# RS232-485.net
KiCad netlist of a schematic drawn in Altium Designer
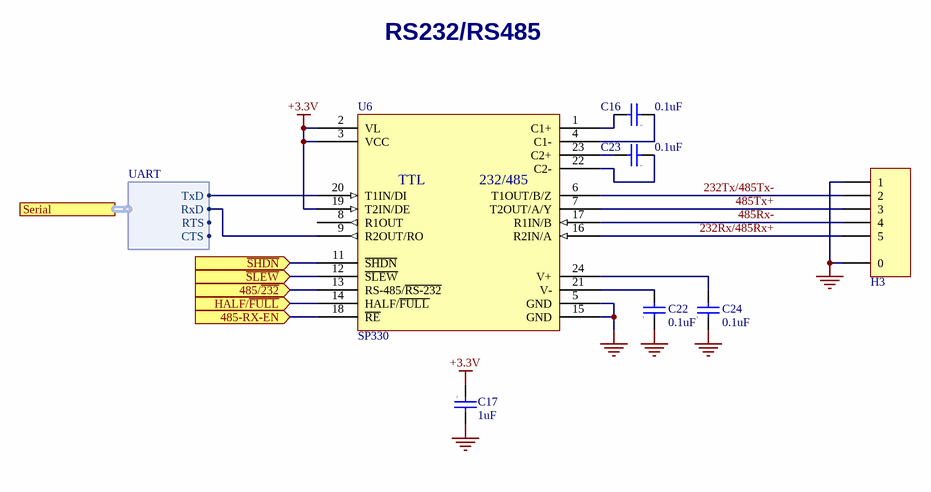
[diagram p0: RS232-485.SchDoc]

(export (version "E")
  (design (tool "Eeschema 10.0.6"))
  (components
    (comp (ref "C16")
      (value "0.1uF")
      (footprint "0402")
      (description "CAP CER .10UF 50V X7R 10% 0402")
      (fields
        (field (name "MANUFACTURER") "TDK Corporation")
        (field (name "MANUFACTURER PART NUMBER") "C1005X7R1H104K")
        (field (name "PUBLISHER") "Altium Limited")
      )
      (libsource (lib "General") (part "Cap"))
    )
    (comp (ref "C17")
      (value "1uF")
      (footprint "0603")
      (description "CAP CER 1UF 25V X7R 0603")
      (fields
        (field (name "MANUFACTURER") "Samsung")
        (field (name "MANUFACTURER PART NUMBER") "CL10B105KA8NNNC")
        (field (name "PUBLISHER") "Altium Limited")
      )
      (libsource (lib "") (part "Cap_2"))
    )
    (comp (ref "C22")
      (value "0.1uF")
      (footprint "0402")
      (description "CAP CER .10UF 50V X7R 10% 0402")
      (fields
        (field (name "MANUFACTURER") "TDK Corporation")
        (field (name "MANUFACTURER PART NUMBER") "C1005X7R1H104K")
        (field (name "PUBLISHER") "Altium Limited")
      )
      (libsource (lib "") (part "Cap_1"))
    )
    (comp (ref "C23")
      (value "0.1uF")
      (footprint "0402")
      (description "CAP CER .10UF 50V X7R 10% 0402")
      (fields
        (field (name "MANUFACTURER") "TDK Corporation")
        (field (name "MANUFACTURER PART NUMBER") "C1005X7R1H104K")
        (field (name "PUBLISHER") "Altium Limited")
      )
      (libsource (lib "General") (part "Cap"))
    )
    (comp (ref "C24")
      (value "0.1uF")
      (footprint "0402")
      (description "CAP CER .10UF 50V X7R 10% 0402")
      (fields
        (field (name "MANUFACTURER") "TDK Corporation")
        (field (name "MANUFACTURER PART NUMBER") "C1005X7R1H104K")
        (field (name "PUBLISHER") "Altium Limited")
      )
      (libsource (lib "") (part "Cap_1"))
    )
    (comp (ref "H3")
      (value "Hdr - 5pin - mount")
      (footprint "SM05B-GHS-TB(LF)(SN)")
      (description "CONN HEADER GH SIDE 5POS 1.25MM")
      (fields
        (field (name "MANUFACTURER") "JST")
        (field (name "MANUFACTURER PART NUMBER") "SM05B-GHS-TB(LF)(SN)")
      )
      (libsource (lib "Connectors") (part "Hdr - 5pin - mount"))
    )
    (comp (ref "U6")
      (value "SP330")
      (footprint "TSOP65P640X120-24N")
      (description "IC TXRX RS232/485 24TSSOP")
      (fields (field (name "MANUFACTURER") "Exar") (field (name "MANUFACTURER PART NUMBER") "SP330EEY-L"))
      (libsource (lib "ICs") (part "SP330"))
    )
  )
  (nets
    (net (code "2") (name "+3.3V") (class "Default")
      (node (ref "C17") (pin "1") (pinfunction "1_1") (pintype "passive"))
      (node (ref "U6") (pin "19") (pinfunction "T2IN/DE_19") (pintype "input"))
      (node (ref "U6") (pin "2") (pinfunction "VL_2") (pintype "passive"))
      (node (ref "U6") (pin "3") (pinfunction "VCC_3") (pintype "passive"))
    )
    (net (code "3") (name "/232Rx{slash}485Rx+") (class "Default")
      (node (ref "H3") (pin "5") (pinfunction "5_5") (pintype "passive"))
      (node (ref "U6") (pin "16") (pinfunction "R2IN/A_16") (pintype "input"))
    )
    (net (code "4") (name "/232Tx{slash}485Tx-") (class "Default")
      (node (ref "H3") (pin "2") (pinfunction "2_2") (pintype "passive"))
      (node (ref "U6") (pin "6") (pinfunction "T1OUT/B/Z_6") (pintype "passive"))
    )
    (net (code "5") (name "/485-RX-EN") (class "Default")
      (node (ref "U6") (pin "18") (pinfunction "RE_18") (pintype "passive"))
    )
    (net (code "6") (name "/485Rx-") (class "Default")
      (node (ref "H3") (pin "4") (pinfunction "4_4") (pintype "passive"))
      (node (ref "U6") (pin "17") (pinfunction "R1IN/B_17") (pintype "input"))
    )
    (net (code "7") (name "/485Tx+") (class "Default")
      (node (ref "H3") (pin "3") (pinfunction "3_3") (pintype "passive"))
      (node (ref "U6") (pin "7") (pinfunction "T2OUT/A/Y_7") (pintype "passive"))
    )
    (net (code "8") (name "/485{slash}~{232}") (class "Default")
      (node (ref "U6") (pin "13") (pinfunction "RS-485/~{RS-232}_13") (pintype "passive"))
    )
    (net (code "9") (name "/HALF{slash}~{FULL}") (class "Default")
      (node (ref "U6") (pin "14") (pinfunction "HALF/~{FULL}_14") (pintype "passive"))
    )
    (net (code "10") (name "/RxD") (class "Default")
      (node (ref "U6") (pin "9") (pinfunction "R2OUT/RO_9") (pintype "output"))
    )
    (net (code "11") (name "/SHDN") (class "Default")
      (node (ref "U6") (pin "11") (pinfunction "SHDN_11") (pintype "passive"))
    )
    (net (code "12") (name "/SLEW") (class "Default")
      (node (ref "U6") (pin "12") (pinfunction "SLEW_12") (pintype "passive"))
    )
    (net (code "13") (name "/TxD") (class "Default")
      (node (ref "U6") (pin "20") (pinfunction "T1IN/DI_20") (pintype "input"))
    )
    (net (code "15") (name "GND") (class "Default")
      (node (ref "C17") (pin "2") (pinfunction "2_2") (pintype "passive"))
      (node (ref "C22") (pin "1") (pinfunction "1_1") (pintype "passive"))
      (node (ref "C24") (pin "1") (pinfunction "1_1") (pintype "passive"))
      (node (ref "H3") (pin "0") (pinfunction "0_0") (pintype "passive"))
      (node (ref "H3") (pin "1") (pinfunction "1_1") (pintype "passive"))
      (node (ref "U6") (pin "15") (pinfunction "GND_15") (pintype "passive"))
      (node (ref "U6") (pin "5") (pinfunction "GND_5") (pintype "passive"))
    )
    (net (code "16") (name "Net-(U6-C1+)") (class "Default")
      (node (ref "C16") (pin "2") (pinfunction "2_2") (pintype "passive"))
      (node (ref "U6") (pin "1") (pinfunction "C1+_1") (pintype "passive"))
    )
    (net (code "17") (name "Net-(U6-C1-)") (class "Default")
      (node (ref "C16") (pin "1") (pinfunction "1_1") (pintype "passive"))
      (node (ref "U6") (pin "4") (pinfunction "C1-_4") (pintype "passive"))
    )
    (net (code "18") (name "Net-(U6-C2+)") (class "Default")
      (node (ref "C23") (pin "2") (pinfunction "2_2") (pintype "passive"))
      (node (ref "U6") (pin "23") (pinfunction "C2+_23") (pintype "passive"))
    )
    (net (code "19") (name "Net-(U6-C2-)") (class "Default")
      (node (ref "C23") (pin "1") (pinfunction "1_1") (pintype "passive"))
      (node (ref "U6") (pin "22") (pinfunction "C2-_22") (pintype "passive"))
    )
    (net (code "20") (name "Net-(U6-V+)") (class "Default")
      (node (ref "C24") (pin "2") (pinfunction "2_2") (pintype "passive"))
      (node (ref "U6") (pin "24") (pinfunction "V+_24") (pintype "passive"))
    )
    (net (code "21") (name "Net-(U6-V-)") (class "Default")
      (node (ref "C22") (pin "2") (pinfunction "2_2") (pintype "passive"))
      (node (ref "U6") (pin "21") (pinfunction "V-_21") (pintype "passive"))
    )
    (net (code "22") (name "unconnected-(U6-R1OUT-Pad8)") (class "Default")
      (node (ref "U6") (pin "8") (pinfunction "R1OUT_8") (pintype "output"))
    )
  )
)
